# PCB-Schematic.net
KiCad netlist of a schematic drawn in Altium Designer
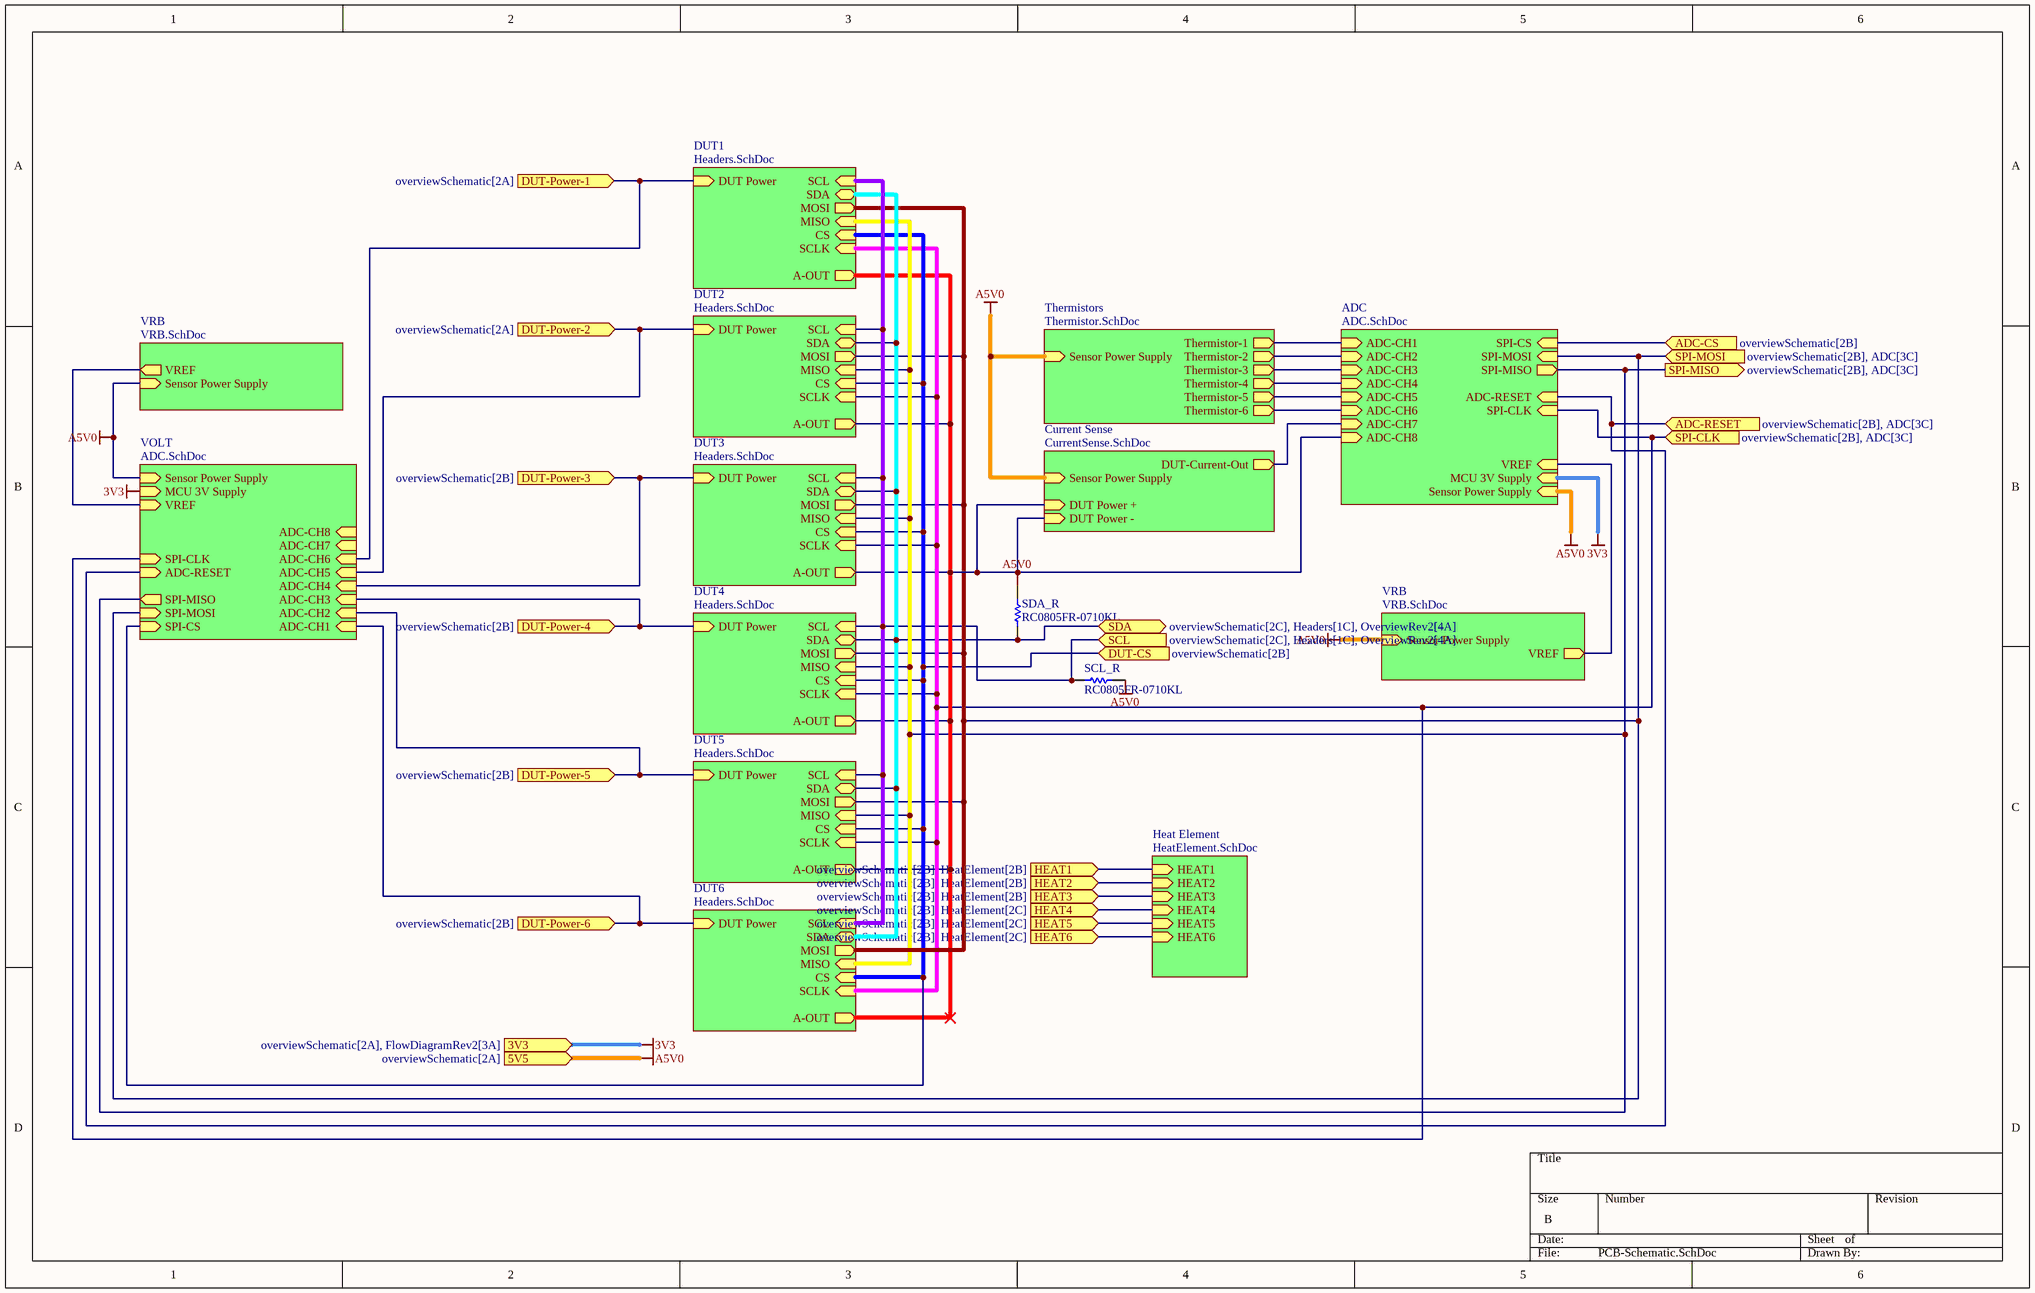
[diagram p0: PCB-Schematic.SchDoc]

(export (version "E")
  (design (tool "Eeschema 10.0.6"))
  (components
    (comp (ref "SCL_R")
      (value "RC0805FR-0710KL")
      (footprint "RESC2013X60X35NL10T20")
      (description "Chip Resistor, 10 KOhm, +/- 1%, 0.125 W, -55 to 155 degC, 0805 (2012 Metric), RoHS, Tape and Reel")
      (fields (field (name "MANUFACTURER") "Yageo"))
      (libsource (lib "PCB-PartsSchematic") (part "RESIST 0805"))
    )
    (comp (ref "SDA_R")
      (value "RC0805FR-0710KL")
      (footprint "RESC2013X60X35NL10T20")
      (description "Chip Resistor, 10 KOhm, +/- 1%, 0.125 W, -55 to 155 degC, 0805 (2012 Metric), RoHS, Tape and Reel")
      (fields (field (name "MANUFACTURER") "Yageo"))
      (libsource (lib "PCB-PartsSchematic") (part "RESIST 0805"))
    )
  )
  (nets
    (net (code "20") (name "/SCL") (class "Default")
      (node (ref "SCL_R") (pin "1") (pinfunction "1_1") (pintype "passive"))
    )
    (net (code "21") (name "/SDA") (class "Default")
      (node (ref "SDA_R") (pin "1") (pinfunction "1_1") (pintype "passive"))
    )
    (net (code "34") (name "A5V0") (class "Default")
      (node (ref "SCL_R") (pin "2") (pinfunction "2_2") (pintype "passive"))
      (node (ref "SDA_R") (pin "2") (pinfunction "2_2") (pintype "passive"))
    )
  )
)
